# SOIC20.net
KiCad netlist of a schematic drawn in Altium Designer
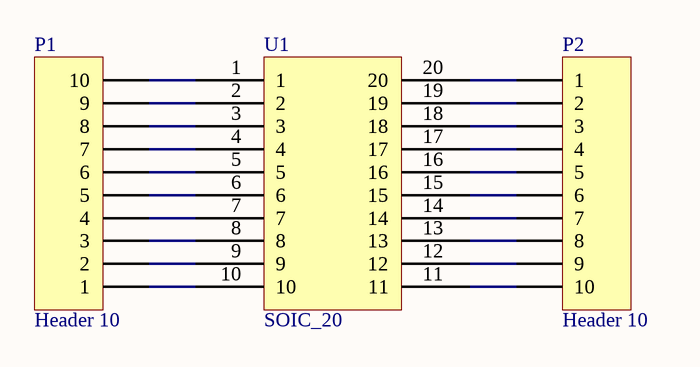
[diagram p0: SOIC20.SchDoc]

(export (version "E")
  (design (tool "Eeschema 10.0.6"))
  (components
    (comp (ref "P1")
      (value "Header 10")
      (footprint "HDR1X10")
      (description "Header, 10-Pin")
      (fields (field (name "PUBLISHER") "Altium Limited"))
      (libsource (lib "Miscellaneous Connectors") (part "Header 10"))
    )
    (comp (ref "P2")
      (value "Header 10")
      (footprint "HDR1X10")
      (description "Header, 10-Pin")
      (fields (field (name "PUBLISHER") "Altium Limited"))
      (libsource (lib "") (part "Header 10_1"))
    )
    (comp (ref "U1")
      (value "SOIC_20")
      (footprint "SOIC20")
      (libsource (lib "PCB_Breakout_Boards") (part "SOIC_20"))
    )
  )
  (nets
    (net (code "1") (name "Net-(P1-Pad1)") (class "Default")
      (node (ref "P1") (pin "1") (pinfunction "1_1") (pintype "passive"))
      (node (ref "U1") (pin "10") (pinfunction "10_10") (pintype "passive"))
    )
    (net (code "2") (name "Net-(P1-Pad2)") (class "Default")
      (node (ref "P1") (pin "2") (pinfunction "2_2") (pintype "passive"))
      (node (ref "U1") (pin "9") (pinfunction "9_9") (pintype "passive"))
    )
    (net (code "3") (name "Net-(P1-Pad3)") (class "Default")
      (node (ref "P1") (pin "3") (pinfunction "3_3") (pintype "passive"))
      (node (ref "U1") (pin "8") (pinfunction "8_8") (pintype "passive"))
    )
    (net (code "4") (name "Net-(P1-Pad4)") (class "Default")
      (node (ref "P1") (pin "4") (pinfunction "4_4") (pintype "passive"))
      (node (ref "U1") (pin "7") (pinfunction "7_7") (pintype "passive"))
    )
    (net (code "5") (name "Net-(P1-Pad5)") (class "Default")
      (node (ref "P1") (pin "5") (pinfunction "5_5") (pintype "passive"))
      (node (ref "U1") (pin "6") (pinfunction "6_6") (pintype "passive"))
    )
    (net (code "6") (name "Net-(P1-Pad6)") (class "Default")
      (node (ref "P1") (pin "6") (pinfunction "6_6") (pintype "passive"))
      (node (ref "U1") (pin "5") (pinfunction "5_5") (pintype "passive"))
    )
    (net (code "7") (name "Net-(P1-Pad7)") (class "Default")
      (node (ref "P1") (pin "7") (pinfunction "7_7") (pintype "passive"))
      (node (ref "U1") (pin "4") (pinfunction "4_4") (pintype "passive"))
    )
    (net (code "8") (name "Net-(P1-Pad8)") (class "Default")
      (node (ref "P1") (pin "8") (pinfunction "8_8") (pintype "passive"))
      (node (ref "U1") (pin "3") (pinfunction "3_3") (pintype "passive"))
    )
    (net (code "9") (name "Net-(P1-Pad9)") (class "Default")
      (node (ref "P1") (pin "9") (pinfunction "9_9") (pintype "passive"))
      (node (ref "U1") (pin "2") (pinfunction "2_2") (pintype "passive"))
    )
    (net (code "10") (name "Net-(P1-Pad10)") (class "Default")
      (node (ref "P1") (pin "10") (pinfunction "10_10") (pintype "passive"))
      (node (ref "U1") (pin "1") (pinfunction "1_1") (pintype "passive"))
    )
    (net (code "11") (name "Net-(P2-Pad1)") (class "Default")
      (node (ref "P2") (pin "1") (pinfunction "1_1") (pintype "passive"))
      (node (ref "U1") (pin "20") (pinfunction "20_20") (pintype "passive"))
    )
    (net (code "12") (name "Net-(P2-Pad2)") (class "Default")
      (node (ref "P2") (pin "2") (pinfunction "2_2") (pintype "passive"))
      (node (ref "U1") (pin "19") (pinfunction "19_19") (pintype "passive"))
    )
    (net (code "13") (name "Net-(P2-Pad3)") (class "Default")
      (node (ref "P2") (pin "3") (pinfunction "3_3") (pintype "passive"))
      (node (ref "U1") (pin "18") (pinfunction "18_18") (pintype "passive"))
    )
    (net (code "14") (name "Net-(P2-Pad4)") (class "Default")
      (node (ref "P2") (pin "4") (pinfunction "4_4") (pintype "passive"))
      (node (ref "U1") (pin "17") (pinfunction "17_17") (pintype "passive"))
    )
    (net (code "15") (name "Net-(P2-Pad5)") (class "Default")
      (node (ref "P2") (pin "5") (pinfunction "5_5") (pintype "passive"))
      (node (ref "U1") (pin "16") (pinfunction "16_16") (pintype "passive"))
    )
    (net (code "16") (name "Net-(P2-Pad6)") (class "Default")
      (node (ref "P2") (pin "6") (pinfunction "6_6") (pintype "passive"))
      (node (ref "U1") (pin "15") (pinfunction "15_15") (pintype "passive"))
    )
    (net (code "17") (name "Net-(P2-Pad7)") (class "Default")
      (node (ref "P2") (pin "7") (pinfunction "7_7") (pintype "passive"))
      (node (ref "U1") (pin "14") (pinfunction "14_14") (pintype "passive"))
    )
    (net (code "18") (name "Net-(P2-Pad8)") (class "Default")
      (node (ref "P2") (pin "8") (pinfunction "8_8") (pintype "passive"))
      (node (ref "U1") (pin "13") (pinfunction "13_13") (pintype "passive"))
    )
    (net (code "19") (name "Net-(P2-Pad9)") (class "Default")
      (node (ref "P2") (pin "9") (pinfunction "9_9") (pintype "passive"))
      (node (ref "U1") (pin "12") (pinfunction "12_12") (pintype "passive"))
    )
    (net (code "20") (name "Net-(P2-Pad10)") (class "Default")
      (node (ref "P2") (pin "10") (pinfunction "10_10") (pintype "passive"))
      (node (ref "U1") (pin "11") (pinfunction "11_11") (pintype "passive"))
    )
  )
)
